# MCU.net
KiCad netlist of a schematic drawn in Altium Designer
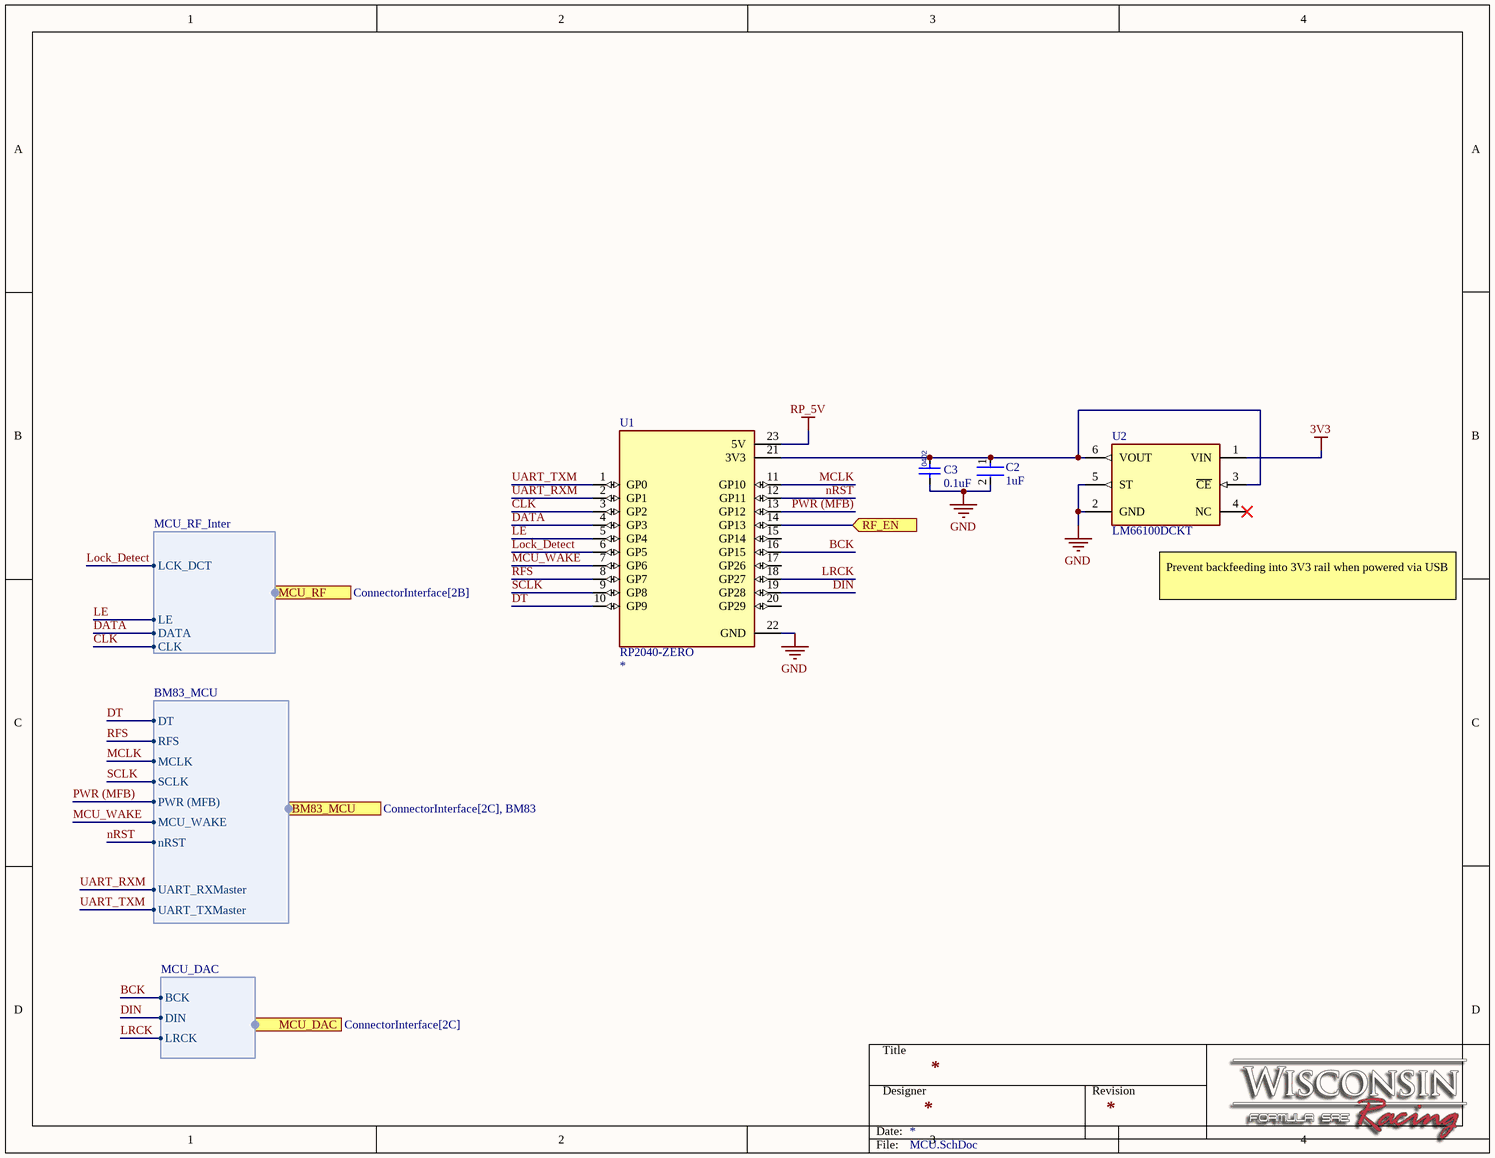
[diagram p0: MCU.SchDoc]

(export (version "E")
  (design (tool "Eeschema 10.0.6"))
  (components
    (comp (ref "C2")
      (value "1uF")
      (footprint "FP-GRM155-0_1-IPC_C")
      (libsource (lib "Altium Content Vault") (part "11868f565c42a9108669ba33697ecf6"))
    )
    (comp (ref "C3")
      (value "0.1uF")
      (footprint "FP-CC0402-IPC_B")
      (fields (field (name "TOLERANCE") "10%"))
      (libsource (lib "University of Wisconsin Formula FSAE") (part "0402 ceramic cap"))
    )
    (comp (ref "U1")
      (value "RP2040-ZERO")
      (footprint "MODULE_RP2040-ZERO")
      (description "Low-Cost, High-Performance Pico-Like MCU Board Based On Raspberry Pi Microcontroller RP2040")
      (fields (field (name "MF") "Waveshare Electronics") (field (name "ALTIUM_VALUE") "*"))
      (libsource (lib "University of Wisconsin Formula FSAE") (part "RP2040-ZERO"))
    )
    (comp (ref "U2")
      (value "LM66100DCKT")
      (footprint "FP-DCK0006A-IPC_C")
      (description "IC OR CTRLR IDEAL DIODE SC70-6")
      (libsource (lib "Altium Content Vault") (part "3595dc506fef48fc1df3095330a4feb"))
    )
  )
  (nets
    (net (code "4") (name "/BCK") (class "Default")
      (node (ref "U1") (pin "16") (pinfunction "GP15_16") (pintype "bidirectional"))
    )
    (net (code "5") (name "/CLK") (class "Default")
      (node (ref "U1") (pin "3") (pinfunction "GP2_3") (pintype "bidirectional"))
    )
    (net (code "6") (name "/DATA") (class "Default")
      (node (ref "U1") (pin "4") (pinfunction "GP3_4") (pintype "bidirectional"))
    )
    (net (code "7") (name "/DIN") (class "Default")
      (node (ref "U1") (pin "19") (pinfunction "GP28_19") (pintype "bidirectional"))
    )
    (net (code "8") (name "/DT") (class "Default")
      (node (ref "U1") (pin "10") (pinfunction "GP9_10") (pintype "bidirectional"))
    )
    (net (code "9") (name "/LE") (class "Default")
      (node (ref "U1") (pin "5") (pinfunction "GP4_5") (pintype "bidirectional"))
    )
    (net (code "10") (name "/LRCK") (class "Default")
      (node (ref "U1") (pin "18") (pinfunction "GP27_18") (pintype "bidirectional"))
    )
    (net (code "11") (name "/Lock_Detect") (class "Default")
      (node (ref "U1") (pin "6") (pinfunction "GP5_6") (pintype "bidirectional"))
    )
    (net (code "12") (name "/MCLK") (class "Default")
      (node (ref "U1") (pin "11") (pinfunction "GP10_11") (pintype "bidirectional"))
    )
    (net (code "13") (name "/MCU_WAKE") (class "Default")
      (node (ref "U1") (pin "7") (pinfunction "GP6_7") (pintype "bidirectional"))
    )
    (net (code "14") (name "/PWR (MFB)") (class "Default")
      (node (ref "U1") (pin "13") (pinfunction "GP12_13") (pintype "bidirectional"))
    )
    (net (code "15") (name "/RFS") (class "Default")
      (node (ref "U1") (pin "8") (pinfunction "GP7_8") (pintype "bidirectional"))
    )
    (net (code "16") (name "/RF_EN") (class "Default")
      (node (ref "U1") (pin "14") (pinfunction "GP13_14") (pintype "bidirectional"))
    )
    (net (code "17") (name "/SCLK") (class "Default")
      (node (ref "U1") (pin "9") (pinfunction "GP8_9") (pintype "bidirectional"))
    )
    (net (code "18") (name "/UART_RXM") (class "Default")
      (node (ref "U1") (pin "2") (pinfunction "GP1_2") (pintype "bidirectional"))
    )
    (net (code "19") (name "/UART_TXM") (class "Default")
      (node (ref "U1") (pin "1") (pinfunction "GP0_1") (pintype "bidirectional"))
    )
    (net (code "20") (name "/nRST") (class "Default")
      (node (ref "U1") (pin "12") (pinfunction "GP11_12") (pintype "bidirectional"))
    )
    (net (code "24") (name "3V3") (class "Default")
      (node (ref "U2") (pin "1") (pinfunction "VIN_1") (pintype "power_in"))
    )
    (net (code "25") (name "GND") (class "Default")
      (node (ref "C2") (pin "2") (pinfunction "2_2") (pintype "passive"))
      (node (ref "C3") (pin "1") (pinfunction "1_1") (pintype "passive"))
      (node (ref "U1") (pin "22") (pinfunction "GND_22") (pintype "power_in"))
      (node (ref "U2") (pin "2") (pinfunction "GND_2") (pintype "power_in"))
      (node (ref "U2") (pin "5") (pinfunction "ST_5") (pintype "output"))
    )
    (net (code "26") (name "Net-(U1-3V3)") (class "Default")
      (node (ref "C2") (pin "1") (pinfunction "1_1") (pintype "passive"))
      (node (ref "C3") (pin "2") (pinfunction "2_2") (pintype "passive"))
      (node (ref "U1") (pin "21") (pinfunction "3V3_21") (pintype "power_in"))
      (node (ref "U2") (pin "3") (pinfunction "~{CE}_3") (pintype "input"))
      (node (ref "U2") (pin "6") (pinfunction "VOUT_6") (pintype "output"))
    )
    (net (code "27") (name "RP_5V") (class "Default")
      (node (ref "U1") (pin "23") (pinfunction "5V_23") (pintype "power_in"))
    )
    (net (code "28") (name "unconnected-(U1-GP14-Pad15)") (class "Default")
      (node (ref "U1") (pin "15") (pinfunction "GP14_15") (pintype "bidirectional"))
    )
    (net (code "29") (name "unconnected-(U1-GP26-Pad17)") (class "Default")
      (node (ref "U1") (pin "17") (pinfunction "GP26_17") (pintype "bidirectional"))
    )
    (net (code "30") (name "unconnected-(U1-GP29-Pad20)") (class "Default")
      (node (ref "U1") (pin "20") (pinfunction "GP29_20") (pintype "bidirectional"))
    )
    (net (code "31") (name "unconnected-(U2-NC-Pad4)") (class "Default")
      (node (ref "U2") (pin "4") (pinfunction "NC_4") (pintype "passive+no_connect"))
    )
  )
)
